# layout.net
KiCad netlist of a schematic drawn in EAGLE
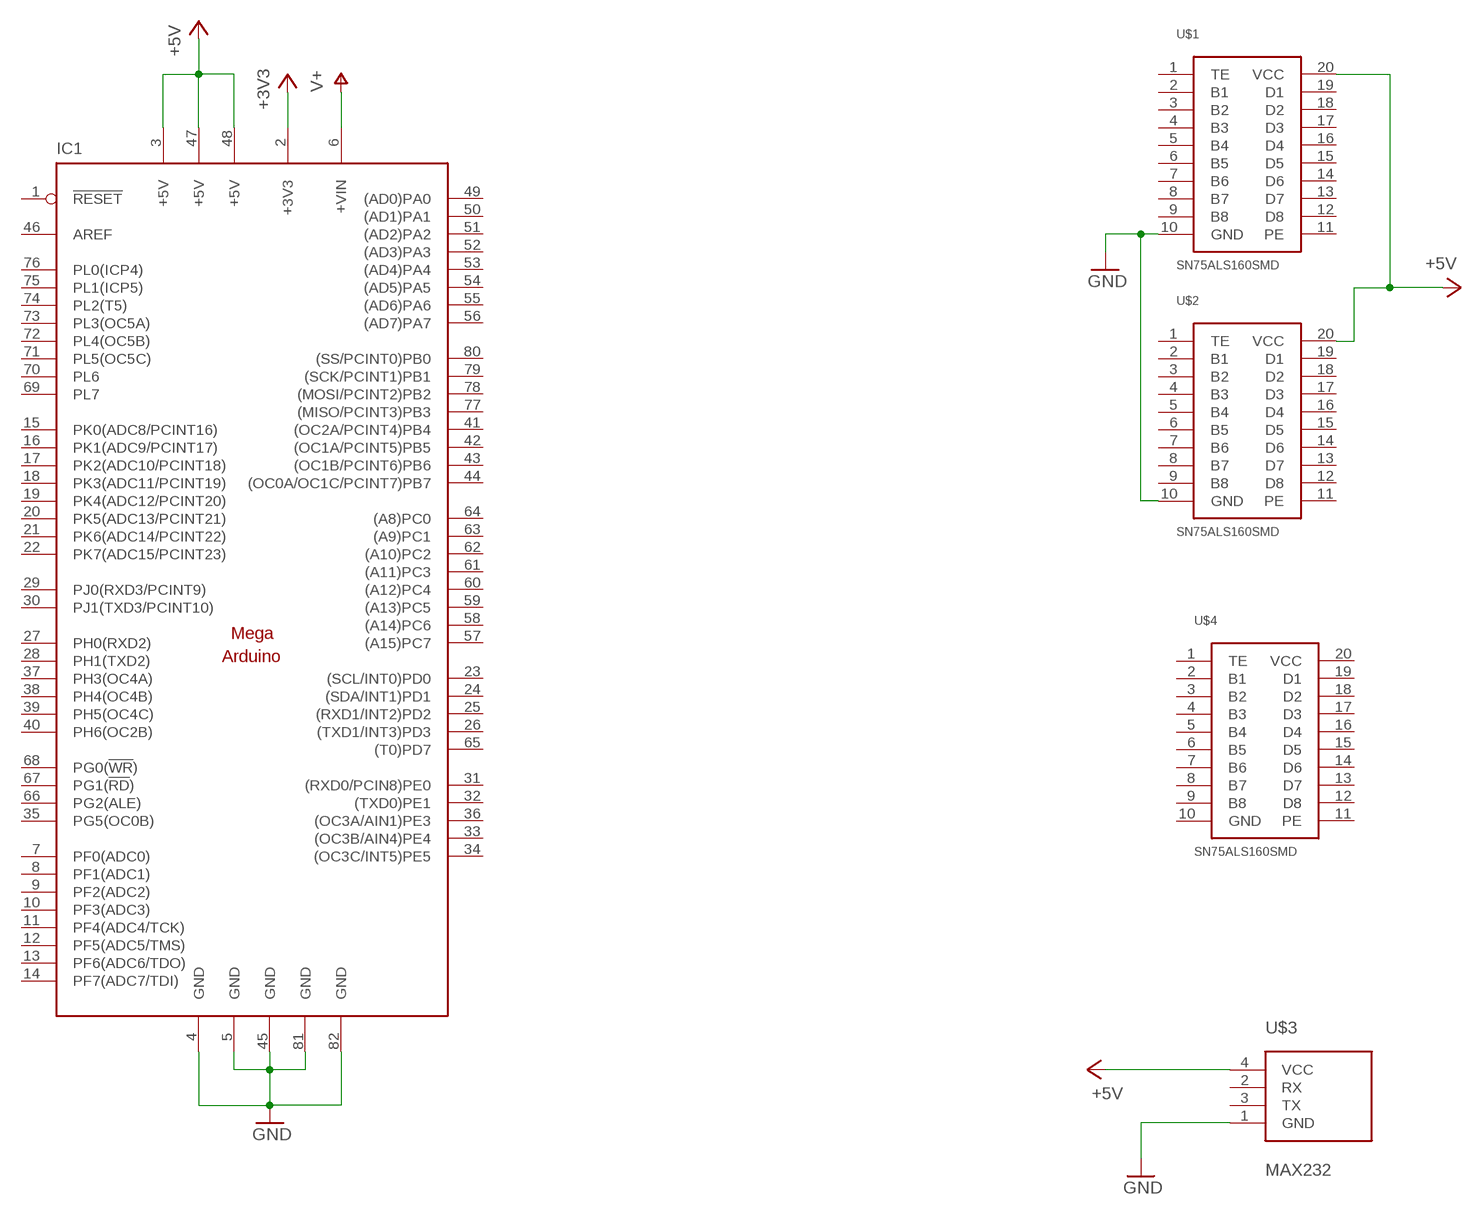
[diagram p0: schematic, sheet 1]

(export (version "E")
  (design (tool "Eeschema 10.0.6"))
  (components
    (comp (ref "IC1")
      (value "Interface")
      (footprint "eagle-import:MEGA_ARDUINO")
      (libsource (lib "eagle-import") (part "MEGAARDUINO_1"))
    )
    (comp (ref "U$1")
      (value "SN75ALS160SMD")
      (footprint "eagle-import:DW0020A")
      (libsource (lib "eagle-import") (part "SN75ALS160SMD"))
    )
    (comp (ref "U$2")
      (value "SN75ALS160SMD")
      (footprint "eagle-import:DW0020A")
      (libsource (lib "eagle-import") (part "SN75ALS160SMD"))
    )
    (comp (ref "U$3")
      (value "MAX232")
      (footprint "eagle-import:4PIN")
      (libsource (lib "eagle-import") (part "MAX232"))
    )
    (comp (ref "U$4")
      (value "SN75ALS160SMD")
      (footprint "eagle-import:DW0020A")
      (libsource (lib "eagle-import") (part "SN75ALS160SMD"))
    )
  )
  (nets
    (net (code "1") (name "+3V3") (class "Default")
      (node (ref "IC1") (pin "2") (pinfunction "+3V3_2") (pintype "power_in"))
    )
    (net (code "2") (name "+5V") (class "Default")
      (node (ref "IC1") (pin "3") (pinfunction "+5V_3") (pintype "power_in"))
      (node (ref "IC1") (pin "47") (pinfunction "+5V_47") (pintype "power_in"))
      (node (ref "IC1") (pin "48") (pinfunction "+5V_48") (pintype "power_in"))
      (node (ref "U$1") (pin "20") (pinfunction "VCC_20") (pintype "bidirectional"))
      (node (ref "U$2") (pin "20") (pinfunction "VCC_20") (pintype "bidirectional"))
      (node (ref "U$3") (pin "4") (pinfunction "VCC_4") (pintype "bidirectional"))
    )
    (net (code "3") (name "GND") (class "Default")
      (node (ref "IC1") (pin "4") (pinfunction "GND_4") (pintype "power_in"))
      (node (ref "IC1") (pin "45") (pinfunction "GND_45") (pintype "power_in"))
      (node (ref "IC1") (pin "5") (pinfunction "GND_5") (pintype "power_in"))
      (node (ref "IC1") (pin "81") (pinfunction "GND_81") (pintype "power_in"))
      (node (ref "IC1") (pin "82") (pinfunction "GND_82") (pintype "power_in"))
      (node (ref "U$1") (pin "10") (pinfunction "GND_10") (pintype "bidirectional"))
      (node (ref "U$2") (pin "10") (pinfunction "GND_10") (pintype "bidirectional"))
      (node (ref "U$3") (pin "1") (pinfunction "GND_1") (pintype "bidirectional"))
    )
    (net (code "4") (name "V+") (class "Default")
      (node (ref "IC1") (pin "6") (pinfunction "+VIN_6") (pintype "power_in"))
    )
    (net (code "5") (name "unconnected-(IC1-(A8)PC0-Pad64)") (class "Default")
      (node (ref "IC1") (pin "64") (pinfunction "(A8)PC0_64") (pintype "bidirectional"))
    )
    (net (code "6") (name "unconnected-(IC1-(A9)PC1-Pad63)") (class "Default")
      (node (ref "IC1") (pin "63") (pinfunction "(A9)PC1_63") (pintype "bidirectional"))
    )
    (net (code "7") (name "unconnected-(IC1-(A10)PC2-Pad62)") (class "Default")
      (node (ref "IC1") (pin "62") (pinfunction "(A10)PC2_62") (pintype "bidirectional"))
    )
    (net (code "8") (name "unconnected-(IC1-(A11)PC3-Pad61)") (class "Default")
      (node (ref "IC1") (pin "61") (pinfunction "(A11)PC3_61") (pintype "bidirectional"))
    )
    (net (code "9") (name "unconnected-(IC1-(A12)PC4-Pad60)") (class "Default")
      (node (ref "IC1") (pin "60") (pinfunction "(A12)PC4_60") (pintype "bidirectional"))
    )
    (net (code "10") (name "unconnected-(IC1-(A13)PC5-Pad59)") (class "Default")
      (node (ref "IC1") (pin "59") (pinfunction "(A13)PC5_59") (pintype "bidirectional"))
    )
    (net (code "11") (name "unconnected-(IC1-(A14)PC6-Pad58)") (class "Default")
      (node (ref "IC1") (pin "58") (pinfunction "(A14)PC6_58") (pintype "bidirectional"))
    )
    (net (code "12") (name "unconnected-(IC1-(A15)PC7-Pad57)") (class "Default")
      (node (ref "IC1") (pin "57") (pinfunction "(A15)PC7_57") (pintype "bidirectional"))
    )
    (net (code "13") (name "unconnected-(IC1-(AD0)PA0-Pad49)") (class "Default")
      (node (ref "IC1") (pin "49") (pinfunction "(AD0)PA0_49") (pintype "bidirectional"))
    )
    (net (code "14") (name "unconnected-(IC1-(AD1)PA1-Pad50)") (class "Default")
      (node (ref "IC1") (pin "50") (pinfunction "(AD1)PA1_50") (pintype "bidirectional"))
    )
    (net (code "15") (name "unconnected-(IC1-(AD2)PA2-Pad51)") (class "Default")
      (node (ref "IC1") (pin "51") (pinfunction "(AD2)PA2_51") (pintype "bidirectional"))
    )
    (net (code "16") (name "unconnected-(IC1-(AD3)PA3-Pad52)") (class "Default")
      (node (ref "IC1") (pin "52") (pinfunction "(AD3)PA3_52") (pintype "bidirectional"))
    )
    (net (code "17") (name "unconnected-(IC1-(AD4)PA4-Pad53)") (class "Default")
      (node (ref "IC1") (pin "53") (pinfunction "(AD4)PA4_53") (pintype "bidirectional"))
    )
    (net (code "18") (name "unconnected-(IC1-(AD5)PA5-Pad54)") (class "Default")
      (node (ref "IC1") (pin "54") (pinfunction "(AD5)PA5_54") (pintype "bidirectional"))
    )
    (net (code "19") (name "unconnected-(IC1-(AD6)PA6-Pad55)") (class "Default")
      (node (ref "IC1") (pin "55") (pinfunction "(AD6)PA6_55") (pintype "bidirectional"))
    )
    (net (code "20") (name "unconnected-(IC1-(AD7)PA7-Pad56)") (class "Default")
      (node (ref "IC1") (pin "56") (pinfunction "(AD7)PA7_56") (pintype "bidirectional"))
    )
    (net (code "21") (name "unconnected-(IC1-(MISO{slash}PCINT3)PB3-Pad77)") (class "Default")
      (node (ref "IC1") (pin "77") (pinfunction "(MISO/PCINT3)PB3_77") (pintype "bidirectional"))
    )
    (net (code "22") (name "unconnected-(IC1-(MOSI{slash}PCINT2)PB2-Pad78)") (class "Default")
      (node (ref "IC1") (pin "78") (pinfunction "(MOSI/PCINT2)PB2_78") (pintype "bidirectional"))
    )
    (net (code "23") (name "unconnected-(IC1-(OC0A{slash}OC1C{slash}PCINT7)PB7-Pad44)") (class "Default")
      (node (ref "IC1") (pin "44") (pinfunction "(OC0A/OC1C/PCINT7)PB7_44") (pintype "bidirectional"))
    )
    (net (code "24") (name "unconnected-(IC1-(OC1A{slash}PCINT5)PB5-Pad42)") (class "Default")
      (node (ref "IC1") (pin "42") (pinfunction "(OC1A/PCINT5)PB5_42") (pintype "bidirectional"))
    )
    (net (code "25") (name "unconnected-(IC1-(OC1B{slash}PCINT6)PB6-Pad43)") (class "Default")
      (node (ref "IC1") (pin "43") (pinfunction "(OC1B/PCINT6)PB6_43") (pintype "bidirectional"))
    )
    (net (code "26") (name "unconnected-(IC1-(OC2A{slash}PCINT4)PB4-Pad41)") (class "Default")
      (node (ref "IC1") (pin "41") (pinfunction "(OC2A/PCINT4)PB4_41") (pintype "bidirectional"))
    )
    (net (code "27") (name "unconnected-(IC1-(OC3A{slash}AIN1)PE3-Pad36)") (class "Default")
      (node (ref "IC1") (pin "36") (pinfunction "(OC3A/AIN1)PE3_36") (pintype "bidirectional"))
    )
    (net (code "28") (name "unconnected-(IC1-(OC3B{slash}AIN4)PE4-Pad33)") (class "Default")
      (node (ref "IC1") (pin "33") (pinfunction "(OC3B/AIN4)PE4_33") (pintype "bidirectional"))
    )
    (net (code "29") (name "unconnected-(IC1-(OC3C{slash}INT5)PE5-Pad34)") (class "Default")
      (node (ref "IC1") (pin "34") (pinfunction "(OC3C/INT5)PE5_34") (pintype "bidirectional"))
    )
    (net (code "30") (name "unconnected-(IC1-(RXD0{slash}PCIN8)PE0-Pad31)") (class "Default")
      (node (ref "IC1") (pin "31") (pinfunction "(RXD0/PCIN8)PE0_31") (pintype "bidirectional"))
    )
    (net (code "31") (name "unconnected-(IC1-(RXD1{slash}INT2)PD2-Pad25)") (class "Default")
      (node (ref "IC1") (pin "25") (pinfunction "(RXD1/INT2)PD2_25") (pintype "bidirectional"))
    )
    (net (code "32") (name "unconnected-(IC1-(SCK{slash}PCINT1)PB1-Pad79)") (class "Default")
      (node (ref "IC1") (pin "79") (pinfunction "(SCK/PCINT1)PB1_79") (pintype "bidirectional"))
    )
    (net (code "33") (name "unconnected-(IC1-(SCL{slash}INT0)PD0-Pad23)") (class "Default")
      (node (ref "IC1") (pin "23") (pinfunction "(SCL/INT0)PD0_23") (pintype "bidirectional"))
    )
    (net (code "34") (name "unconnected-(IC1-(SDA{slash}INT1)PD1-Pad24)") (class "Default")
      (node (ref "IC1") (pin "24") (pinfunction "(SDA/INT1)PD1_24") (pintype "bidirectional"))
    )
    (net (code "35") (name "unconnected-(IC1-(SS{slash}PCINT0)PB0-Pad80)") (class "Default")
      (node (ref "IC1") (pin "80") (pinfunction "(SS/PCINT0)PB0_80") (pintype "bidirectional"))
    )
    (net (code "36") (name "unconnected-(IC1-(T0)PD7-Pad65)") (class "Default")
      (node (ref "IC1") (pin "65") (pinfunction "(T0)PD7_65") (pintype "bidirectional"))
    )
    (net (code "37") (name "unconnected-(IC1-(TXD0)PE1-Pad32)") (class "Default")
      (node (ref "IC1") (pin "32") (pinfunction "(TXD0)PE1_32") (pintype "bidirectional"))
    )
    (net (code "38") (name "unconnected-(IC1-(TXD1{slash}INT3)PD3-Pad26)") (class "Default")
      (node (ref "IC1") (pin "26") (pinfunction "(TXD1/INT3)PD3_26") (pintype "bidirectional"))
    )
    (net (code "39") (name "unconnected-(IC1-AREF-Pad46)") (class "Default")
      (node (ref "IC1") (pin "46") (pinfunction "AREF_46") (pintype "bidirectional"))
    )
    (net (code "40") (name "unconnected-(IC1-PF0(ADC0)-Pad7)") (class "Default")
      (node (ref "IC1") (pin "7") (pinfunction "PF0(ADC0)_7") (pintype "bidirectional"))
    )
    (net (code "41") (name "unconnected-(IC1-PF1(ADC1)-Pad8)") (class "Default")
      (node (ref "IC1") (pin "8") (pinfunction "PF1(ADC1)_8") (pintype "bidirectional"))
    )
    (net (code "42") (name "unconnected-(IC1-PF2(ADC2)-Pad9)") (class "Default")
      (node (ref "IC1") (pin "9") (pinfunction "PF2(ADC2)_9") (pintype "bidirectional"))
    )
    (net (code "43") (name "unconnected-(IC1-PF3(ADC3)-Pad10)") (class "Default")
      (node (ref "IC1") (pin "10") (pinfunction "PF3(ADC3)_10") (pintype "bidirectional"))
    )
    (net (code "44") (name "unconnected-(IC1-PF4(ADC4{slash}TCK)-Pad11)") (class "Default")
      (node (ref "IC1") (pin "11") (pinfunction "PF4(ADC4/TCK)_11") (pintype "bidirectional"))
    )
    (net (code "45") (name "unconnected-(IC1-PF5(ADC5{slash}TMS)-Pad12)") (class "Default")
      (node (ref "IC1") (pin "12") (pinfunction "PF5(ADC5/TMS)_12") (pintype "bidirectional"))
    )
    (net (code "46") (name "unconnected-(IC1-PF6(ADC6{slash}TDO)-Pad13)") (class "Default")
      (node (ref "IC1") (pin "13") (pinfunction "PF6(ADC6/TDO)_13") (pintype "bidirectional"))
    )
    (net (code "47") (name "unconnected-(IC1-PF7(ADC7{slash}TDI)-Pad14)") (class "Default")
      (node (ref "IC1") (pin "14") (pinfunction "PF7(ADC7/TDI)_14") (pintype "bidirectional"))
    )
    (net (code "48") (name "unconnected-(IC1-PG0(~{WR})-Pad68)") (class "Default")
      (node (ref "IC1") (pin "68") (pinfunction "PG0(~{WR})_68") (pintype "bidirectional"))
    )
    (net (code "49") (name "unconnected-(IC1-PG1(~{RD})-Pad67)") (class "Default")
      (node (ref "IC1") (pin "67") (pinfunction "PG1(~{RD})_67") (pintype "bidirectional"))
    )
    (net (code "50") (name "unconnected-(IC1-PG2(ALE)-Pad66)") (class "Default")
      (node (ref "IC1") (pin "66") (pinfunction "PG2(ALE)_66") (pintype "bidirectional"))
    )
    (net (code "51") (name "unconnected-(IC1-PG5(OC0B)-Pad35)") (class "Default")
      (node (ref "IC1") (pin "35") (pinfunction "PG5(OC0B)_35") (pintype "bidirectional"))
    )
    (net (code "52") (name "unconnected-(IC1-PH0(RXD2)-Pad27)") (class "Default")
      (node (ref "IC1") (pin "27") (pinfunction "PH0(RXD2)_27") (pintype "bidirectional"))
    )
    (net (code "53") (name "unconnected-(IC1-PH1(TXD2)-Pad28)") (class "Default")
      (node (ref "IC1") (pin "28") (pinfunction "PH1(TXD2)_28") (pintype "bidirectional"))
    )
    (net (code "54") (name "unconnected-(IC1-PH3(OC4A)-Pad37)") (class "Default")
      (node (ref "IC1") (pin "37") (pinfunction "PH3(OC4A)_37") (pintype "bidirectional"))
    )
    (net (code "55") (name "unconnected-(IC1-PH4(OC4B)-Pad38)") (class "Default")
      (node (ref "IC1") (pin "38") (pinfunction "PH4(OC4B)_38") (pintype "bidirectional"))
    )
    (net (code "56") (name "unconnected-(IC1-PH5(OC4C)-Pad39)") (class "Default")
      (node (ref "IC1") (pin "39") (pinfunction "PH5(OC4C)_39") (pintype "bidirectional"))
    )
    (net (code "57") (name "unconnected-(IC1-PH6(OC2B)-Pad40)") (class "Default")
      (node (ref "IC1") (pin "40") (pinfunction "PH6(OC2B)_40") (pintype "bidirectional"))
    )
    (net (code "58") (name "unconnected-(IC1-PJ0(RXD3{slash}PCINT9)-Pad29)") (class "Default")
      (node (ref "IC1") (pin "29") (pinfunction "PJ0(RXD3/PCINT9)_29") (pintype "bidirectional"))
    )
    (net (code "59") (name "unconnected-(IC1-PJ1(TXD3{slash}PCINT10)-Pad30)") (class "Default")
      (node (ref "IC1") (pin "30") (pinfunction "PJ1(TXD3/PCINT10)_30") (pintype "bidirectional"))
    )
    (net (code "60") (name "unconnected-(IC1-PK0(ADC8{slash}PCINT16)-Pad15)") (class "Default")
      (node (ref "IC1") (pin "15") (pinfunction "PK0(ADC8/PCINT16)_15") (pintype "bidirectional"))
    )
    (net (code "61") (name "unconnected-(IC1-PK1(ADC9{slash}PCINT17)-Pad16)") (class "Default")
      (node (ref "IC1") (pin "16") (pinfunction "PK1(ADC9/PCINT17)_16") (pintype "bidirectional"))
    )
    (net (code "62") (name "unconnected-(IC1-PK2(ADC10{slash}PCINT18)-Pad17)") (class "Default")
      (node (ref "IC1") (pin "17") (pinfunction "PK2(ADC10/PCINT18)_17") (pintype "bidirectional"))
    )
    (net (code "63") (name "unconnected-(IC1-PK3(ADC11{slash}PCINT19)-Pad18)") (class "Default")
      (node (ref "IC1") (pin "18") (pinfunction "PK3(ADC11/PCINT19)_18") (pintype "bidirectional"))
    )
    (net (code "64") (name "unconnected-(IC1-PK4(ADC12{slash}PCINT20)-Pad19)") (class "Default")
      (node (ref "IC1") (pin "19") (pinfunction "PK4(ADC12/PCINT20)_19") (pintype "bidirectional"))
    )
    (net (code "65") (name "unconnected-(IC1-PK5(ADC13{slash}PCINT21)-Pad20)") (class "Default")
      (node (ref "IC1") (pin "20") (pinfunction "PK5(ADC13/PCINT21)_20") (pintype "bidirectional"))
    )
    (net (code "66") (name "unconnected-(IC1-PK6(ADC14{slash}PCINT22)-Pad21)") (class "Default")
      (node (ref "IC1") (pin "21") (pinfunction "PK6(ADC14/PCINT22)_21") (pintype "bidirectional"))
    )
    (net (code "67") (name "unconnected-(IC1-PK7(ADC15{slash}PCINT23)-Pad22)") (class "Default")
      (node (ref "IC1") (pin "22") (pinfunction "PK7(ADC15/PCINT23)_22") (pintype "bidirectional"))
    )
    (net (code "68") (name "unconnected-(IC1-PL0(ICP4)-Pad76)") (class "Default")
      (node (ref "IC1") (pin "76") (pinfunction "PL0(ICP4)_76") (pintype "bidirectional"))
    )
    (net (code "69") (name "unconnected-(IC1-PL1(ICP5)-Pad75)") (class "Default")
      (node (ref "IC1") (pin "75") (pinfunction "PL1(ICP5)_75") (pintype "bidirectional"))
    )
    (net (code "70") (name "unconnected-(IC1-PL2(T5)-Pad74)") (class "Default")
      (node (ref "IC1") (pin "74") (pinfunction "PL2(T5)_74") (pintype "bidirectional"))
    )
    (net (code "71") (name "unconnected-(IC1-PL3(OC5A)-Pad73)") (class "Default")
      (node (ref "IC1") (pin "73") (pinfunction "PL3(OC5A)_73") (pintype "bidirectional"))
    )
    (net (code "72") (name "unconnected-(IC1-PL4(OC5B)-Pad72)") (class "Default")
      (node (ref "IC1") (pin "72") (pinfunction "PL4(OC5B)_72") (pintype "bidirectional"))
    )
    (net (code "73") (name "unconnected-(IC1-PL5(OC5C)-Pad71)") (class "Default")
      (node (ref "IC1") (pin "71") (pinfunction "PL5(OC5C)_71") (pintype "bidirectional"))
    )
    (net (code "74") (name "unconnected-(IC1-PL6-Pad70)") (class "Default")
      (node (ref "IC1") (pin "70") (pinfunction "PL6_70") (pintype "bidirectional"))
    )
    (net (code "75") (name "unconnected-(IC1-PL7-Pad69)") (class "Default")
      (node (ref "IC1") (pin "69") (pinfunction "PL7_69") (pintype "bidirectional"))
    )
    (net (code "76") (name "unconnected-(IC1-~{RESET}-Pad1)") (class "Default")
      (node (ref "IC1") (pin "1") (pinfunction "~{RESET}_1") (pintype "bidirectional"))
    )
    (net (code "77") (name "unconnected-(U$1-B1-Pad2)") (class "Default")
      (node (ref "U$1") (pin "2") (pinfunction "B1_2") (pintype "bidirectional"))
    )
    (net (code "78") (name "unconnected-(U$1-B2-Pad3)") (class "Default")
      (node (ref "U$1") (pin "3") (pinfunction "B2_3") (pintype "bidirectional"))
    )
    (net (code "79") (name "unconnected-(U$1-B3-Pad4)") (class "Default")
      (node (ref "U$1") (pin "4") (pinfunction "B3_4") (pintype "bidirectional"))
    )
    (net (code "80") (name "unconnected-(U$1-B4-Pad5)") (class "Default")
      (node (ref "U$1") (pin "5") (pinfunction "B4_5") (pintype "bidirectional"))
    )
    (net (code "81") (name "unconnected-(U$1-B5-Pad6)") (class "Default")
      (node (ref "U$1") (pin "6") (pinfunction "B5_6") (pintype "bidirectional"))
    )
    (net (code "82") (name "unconnected-(U$1-B6-Pad7)") (class "Default")
      (node (ref "U$1") (pin "7") (pinfunction "B6_7") (pintype "bidirectional"))
    )
    (net (code "83") (name "unconnected-(U$1-B7-Pad8)") (class "Default")
      (node (ref "U$1") (pin "8") (pinfunction "B7_8") (pintype "bidirectional"))
    )
    (net (code "84") (name "unconnected-(U$1-B8-Pad9)") (class "Default")
      (node (ref "U$1") (pin "9") (pinfunction "B8_9") (pintype "bidirectional"))
    )
    (net (code "85") (name "unconnected-(U$1-D1-Pad19)") (class "Default")
      (node (ref "U$1") (pin "19") (pinfunction "D1_19") (pintype "bidirectional"))
    )
    (net (code "86") (name "unconnected-(U$1-D2-Pad18)") (class "Default")
      (node (ref "U$1") (pin "18") (pinfunction "D2_18") (pintype "bidirectional"))
    )
    (net (code "87") (name "unconnected-(U$1-D3-Pad17)") (class "Default")
      (node (ref "U$1") (pin "17") (pinfunction "D3_17") (pintype "bidirectional"))
    )
    (net (code "88") (name "unconnected-(U$1-D4-Pad16)") (class "Default")
      (node (ref "U$1") (pin "16") (pinfunction "D4_16") (pintype "bidirectional"))
    )
    (net (code "89") (name "unconnected-(U$1-D5-Pad15)") (class "Default")
      (node (ref "U$1") (pin "15") (pinfunction "D5_15") (pintype "bidirectional"))
    )
    (net (code "90") (name "unconnected-(U$1-D6-Pad14)") (class "Default")
      (node (ref "U$1") (pin "14") (pinfunction "D6_14") (pintype "bidirectional"))
    )
    (net (code "91") (name "unconnected-(U$1-D7-Pad13)") (class "Default")
      (node (ref "U$1") (pin "13") (pinfunction "D7_13") (pintype "bidirectional"))
    )
    (net (code "92") (name "unconnected-(U$1-D8-Pad12)") (class "Default")
      (node (ref "U$1") (pin "12") (pinfunction "D8_12") (pintype "bidirectional"))
    )
    (net (code "93") (name "unconnected-(U$1-PE-Pad11)") (class "Default")
      (node (ref "U$1") (pin "11") (pinfunction "PE_11") (pintype "bidirectional"))
    )
    (net (code "94") (name "unconnected-(U$1-TE-Pad1)") (class "Default")
      (node (ref "U$1") (pin "1") (pinfunction "TE_1") (pintype "bidirectional"))
    )
    (net (code "95") (name "unconnected-(U$2-B1-Pad2)") (class "Default")
      (node (ref "U$2") (pin "2") (pinfunction "B1_2") (pintype "bidirectional"))
    )
    (net (code "96") (name "unconnected-(U$2-B2-Pad3)") (class "Default")
      (node (ref "U$2") (pin "3") (pinfunction "B2_3") (pintype "bidirectional"))
    )
    (net (code "97") (name "unconnected-(U$2-B3-Pad4)") (class "Default")
      (node (ref "U$2") (pin "4") (pinfunction "B3_4") (pintype "bidirectional"))
    )
    (net (code "98") (name "unconnected-(U$2-B4-Pad5)") (class "Default")
      (node (ref "U$2") (pin "5") (pinfunction "B4_5") (pintype "bidirectional"))
    )
    (net (code "99") (name "unconnected-(U$2-B5-Pad6)") (class "Default")
      (node (ref "U$2") (pin "6") (pinfunction "B5_6") (pintype "bidirectional"))
    )
    (net (code "100") (name "unconnected-(U$2-B6-Pad7)") (class "Default")
      (node (ref "U$2") (pin "7") (pinfunction "B6_7") (pintype "bidirectional"))
    )
    (net (code "101") (name "unconnected-(U$2-B7-Pad8)") (class "Default")
      (node (ref "U$2") (pin "8") (pinfunction "B7_8") (pintype "bidirectional"))
    )
    (net (code "102") (name "unconnected-(U$2-B8-Pad9)") (class "Default")
      (node (ref "U$2") (pin "9") (pinfunction "B8_9") (pintype "bidirectional"))
    )
    (net (code "103") (name "unconnected-(U$2-D1-Pad19)") (class "Default")
      (node (ref "U$2") (pin "19") (pinfunction "D1_19") (pintype "bidirectional"))
    )
    (net (code "104") (name "unconnected-(U$2-D2-Pad18)") (class "Default")
      (node (ref "U$2") (pin "18") (pinfunction "D2_18") (pintype "bidirectional"))
    )
    (net (code "105") (name "unconnected-(U$2-D3-Pad17)") (class "Default")
      (node (ref "U$2") (pin "17") (pinfunction "D3_17") (pintype "bidirectional"))
    )
    (net (code "106") (name "unconnected-(U$2-D4-Pad16)") (class "Default")
      (node (ref "U$2") (pin "16") (pinfunction "D4_16") (pintype "bidirectional"))
    )
    (net (code "107") (name "unconnected-(U$2-D5-Pad15)") (class "Default")
      (node (ref "U$2") (pin "15") (pinfunction "D5_15") (pintype "bidirectional"))
    )
    (net (code "108") (name "unconnected-(U$2-D6-Pad14)") (class "Default")
      (node (ref "U$2") (pin "14") (pinfunction "D6_14") (pintype "bidirectional"))
    )
    (net (code "109") (name "unconnected-(U$2-D7-Pad13)") (class "Default")
      (node (ref "U$2") (pin "13") (pinfunction "D7_13") (pintype "bidirectional"))
    )
    (net (code "110") (name "unconnected-(U$2-D8-Pad12)") (class "Default")
      (node (ref "U$2") (pin "12") (pinfunction "D8_12") (pintype "bidirectional"))
    )
    (net (code "111") (name "unconnected-(U$2-PE-Pad11)") (class "Default")
      (node (ref "U$2") (pin "11") (pinfunction "PE_11") (pintype "bidirectional"))
    )
    (net (code "112") (name "unconnected-(U$2-TE-Pad1)") (class "Default")
      (node (ref "U$2") (pin "1") (pinfunction "TE_1") (pintype "bidirectional"))
    )
    (net (code "113") (name "unconnected-(U$3-RX-Pad2)") (class "Default")
      (node (ref "U$3") (pin "2") (pinfunction "RX_2") (pintype "bidirectional"))
    )
    (net (code "114") (name "unconnected-(U$3-TX-Pad3)") (class "Default")
      (node (ref "U$3") (pin "3") (pinfunction "TX_3") (pintype "bidirectional"))
    )
    (net (code "115") (name "unconnected-(U$4-B1-Pad2)") (class "Default")
      (node (ref "U$4") (pin "2") (pinfunction "B1_2") (pintype "bidirectional"))
    )
    (net (code "116") (name "unconnected-(U$4-B2-Pad3)") (class "Default")
      (node (ref "U$4") (pin "3") (pinfunction "B2_3") (pintype "bidirectional"))
    )
    (net (code "117") (name "unconnected-(U$4-B3-Pad4)") (class "Default")
      (node (ref "U$4") (pin "4") (pinfunction "B3_4") (pintype "bidirectional"))
    )
    (net (code "118") (name "unconnected-(U$4-B4-Pad5)") (class "Default")
      (node (ref "U$4") (pin "5") (pinfunction "B4_5") (pintype "bidirectional"))
    )
    (net (code "119") (name "unconnected-(U$4-B5-Pad6)") (class "Default")
      (node (ref "U$4") (pin "6") (pinfunction "B5_6") (pintype "bidirectional"))
    )
    (net (code "120") (name "unconnected-(U$4-B6-Pad7)") (class "Default")
      (node (ref "U$4") (pin "7") (pinfunction "B6_7") (pintype "bidirectional"))
    )
    (net (code "121") (name "unconnected-(U$4-B7-Pad8)") (class "Default")
      (node (ref "U$4") (pin "8") (pinfunction "B7_8") (pintype "bidirectional"))
    )
    (net (code "122") (name "unconnected-(U$4-B8-Pad9)") (class "Default")
      (node (ref "U$4") (pin "9") (pinfunction "B8_9") (pintype "bidirectional"))
    )
    (net (code "123") (name "unconnected-(U$4-D1-Pad19)") (class "Default")
      (node (ref "U$4") (pin "19") (pinfunction "D1_19") (pintype "bidirectional"))
    )
    (net (code "124") (name "unconnected-(U$4-D2-Pad18)") (class "Default")
      (node (ref "U$4") (pin "18") (pinfunction "D2_18") (pintype "bidirectional"))
    )
    (net (code "125") (name "unconnected-(U$4-D3-Pad17)") (class "Default")
      (node (ref "U$4") (pin "17") (pinfunction "D3_17") (pintype "bidirectional"))
    )
    (net (code "126") (name "unconnected-(U$4-D4-Pad16)") (class "Default")
      (node (ref "U$4") (pin "16") (pinfunction "D4_16") (pintype "bidirectional"))
    )
    (net (code "127") (name "unconnected-(U$4-D5-Pad15)") (class "Default")
      (node (ref "U$4") (pin "15") (pinfunction "D5_15") (pintype "bidirectional"))
    )
    (net (code "128") (name "unconnected-(U$4-D6-Pad14)") (class "Default")
      (node (ref "U$4") (pin "14") (pinfunction "D6_14") (pintype "bidirectional"))
    )
    (net (code "129") (name "unconnected-(U$4-D7-Pad13)") (class "Default")
      (node (ref "U$4") (pin "13") (pinfunction "D7_13") (pintype "bidirectional"))
    )
    (net (code "130") (name "unconnected-(U$4-D8-Pad12)") (class "Default")
      (node (ref "U$4") (pin "12") (pinfunction "D8_12") (pintype "bidirectional"))
    )
    (net (code "131") (name "unconnected-(U$4-GND-Pad10)") (class "Default")
      (node (ref "U$4") (pin "10") (pinfunction "GND_10") (pintype "bidirectional"))
    )
    (net (code "132") (name "unconnected-(U$4-PE-Pad11)") (class "Default")
      (node (ref "U$4") (pin "11") (pinfunction "PE_11") (pintype "bidirectional"))
    )
    (net (code "133") (name "unconnected-(U$4-TE-Pad1)") (class "Default")
      (node (ref "U$4") (pin "1") (pinfunction "TE_1") (pintype "bidirectional"))
    )
    (net (code "134") (name "unconnected-(U$4-VCC-Pad20)") (class "Default")
      (node (ref "U$4") (pin "20") (pinfunction "VCC_20") (pintype "bidirectional"))
    )
  )
)
